# Wifinfo.net
KiCad netlist of a schematic drawn in EAGLE
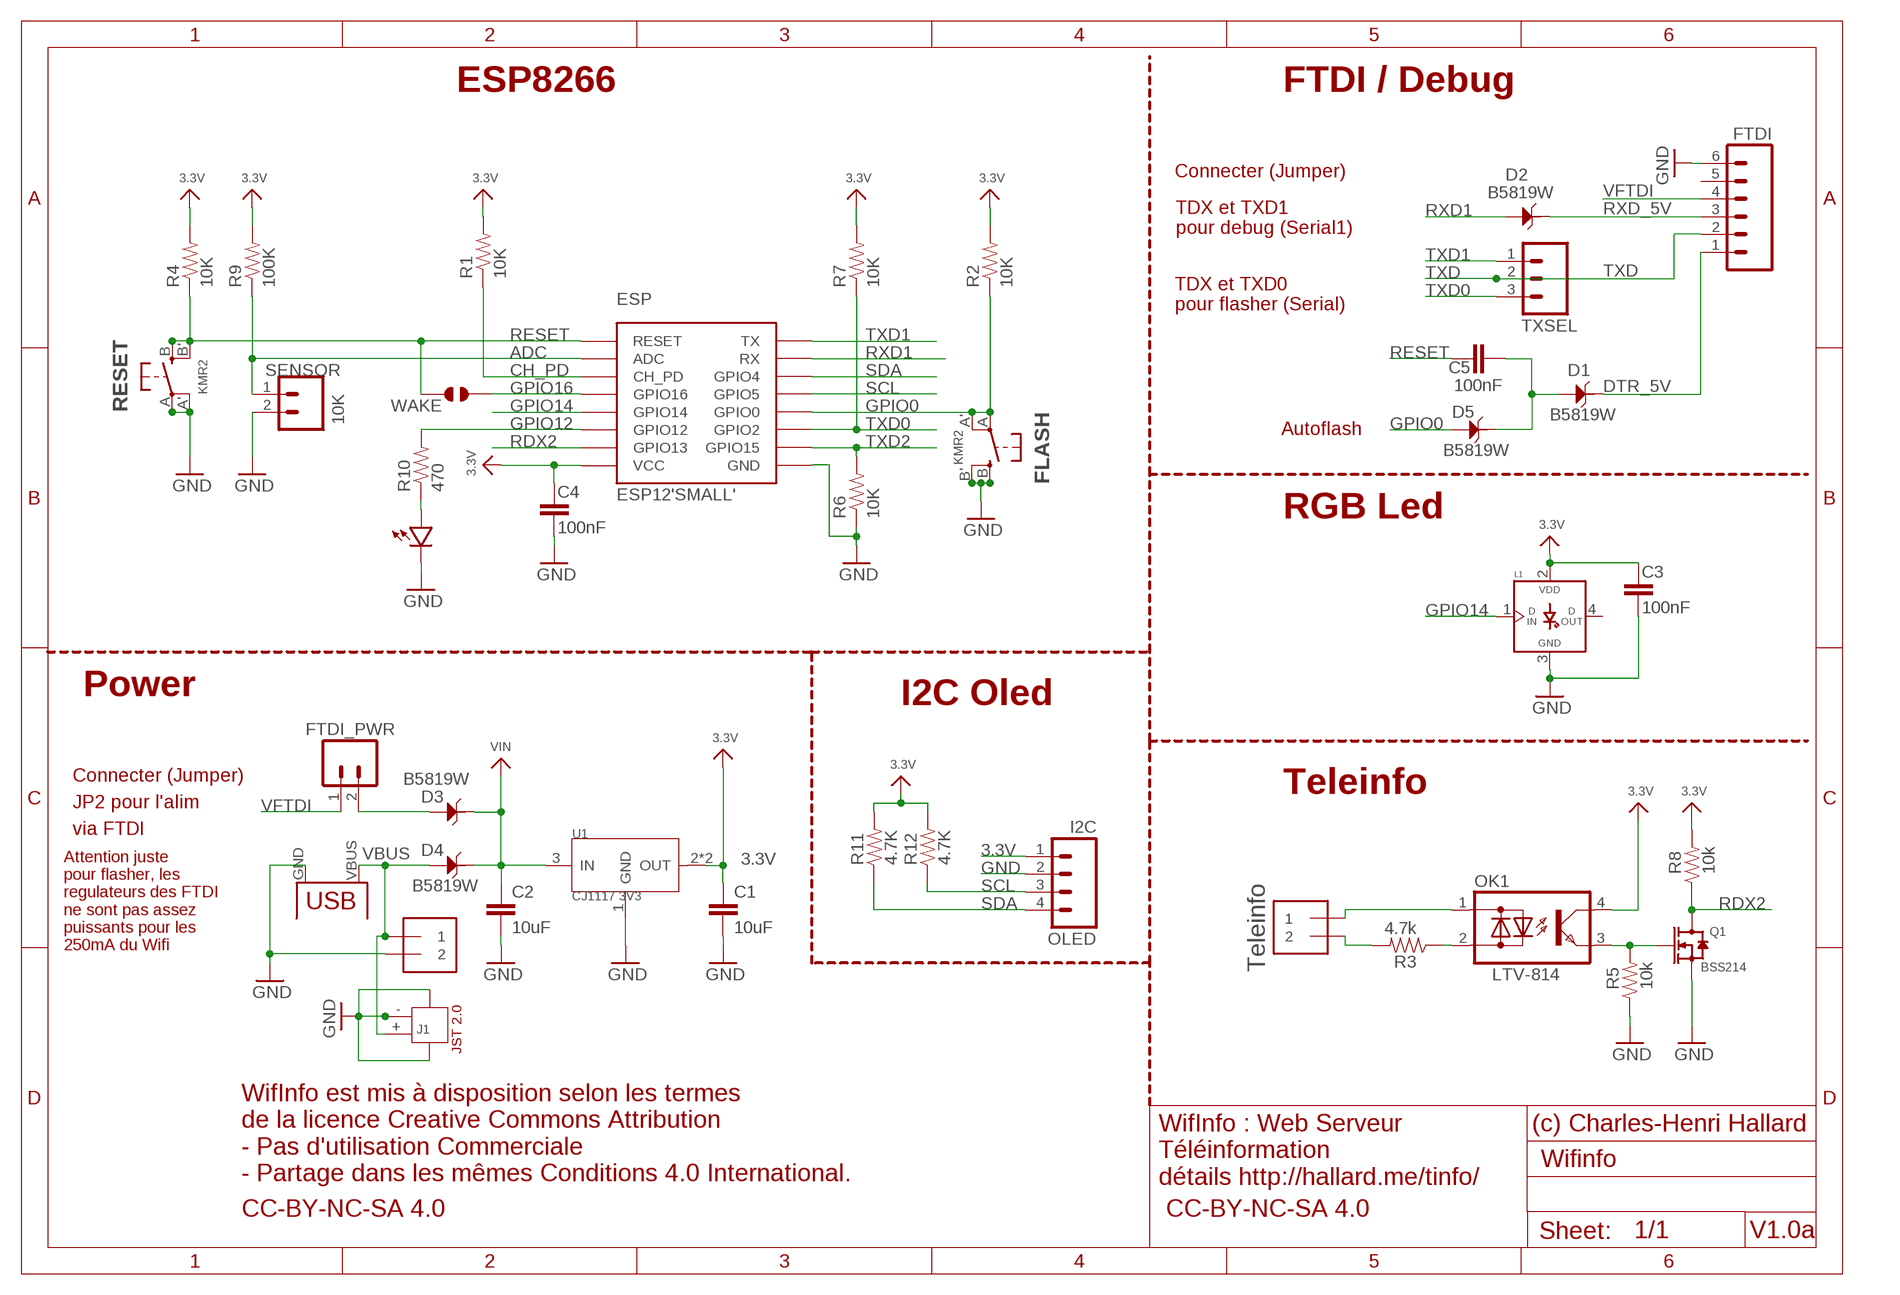
[diagram p0: schematic, sheet 1]

(export (version "E")
  (design (tool "Eeschema 10.0.6"))
  (components
    (comp (ref "C1")
      (value "10uF")
      (footprint "eagle-import:0805-CAP")
      (libsource (lib "eagle-import") (part "CAP0805-CAP"))
    )
    (comp (ref "C2")
      (value "10uF")
      (footprint "eagle-import:0805-CAP")
      (libsource (lib "eagle-import") (part "CAP0805-CAP"))
    )
    (comp (ref "C3")
      (value "100nF")
      (footprint "eagle-import:0603-CAP")
      (libsource (lib "eagle-import") (part "CAP0603-CAP"))
    )
    (comp (ref "C4")
      (value "100nF")
      (footprint "eagle-import:0603-CAP")
      (libsource (lib "eagle-import") (part "CAP0603-CAP"))
    )
    (comp (ref "C5")
      (value "100nF")
      (footprint "eagle-import:0603-CAP")
      (libsource (lib "eagle-import") (part "CAP0603-CAP"))
    )
    (comp (ref "D1")
      (value "B5819W")
      (footprint "eagle-import:SOD123-2.7X1.6")
      (libsource (lib "eagle-import") (part "D-ESD-2P-CESD5V0D1"))
    )
    (comp (ref "D2")
      (value "B5819W")
      (footprint "eagle-import:SOD123-2.7X1.6")
      (libsource (lib "eagle-import") (part "D-ESD-2P-CESD5V0D1"))
    )
    (comp (ref "D3")
      (value "B5819W")
      (footprint "eagle-import:SOD123-2.7X1.6")
      (libsource (lib "eagle-import") (part "D-ESD-2P-CESD5V0D1"))
    )
    (comp (ref "D4")
      (value "B5819W")
      (footprint "eagle-import:SOD123-2.7X1.6")
      (libsource (lib "eagle-import") (part "D-ESD-2P-CESD5V0D1"))
    )
    (comp (ref "D5")
      (value "B5819W")
      (footprint "eagle-import:SOD123-2.7X1.6")
      (libsource (lib "eagle-import") (part "D-ESD-2P-CESD5V0D1"))
    )
    (comp (ref "ESP")
      (value "ESP12'SMALL'")
      (footprint "eagle-import:ESP08")
      (libsource (lib "eagle-import") (part "ESP12'SMALL'"))
    )
    (comp (ref "FLASH")
      (value "KMR2")
      (footprint "eagle-import:BTN_KMR2_4.6X2.8")
      (libsource (lib "eagle-import") (part "SWITCH_TACT_SMT4.6X2.8"))
    )
    (comp (ref "FTDI")
      (value "M06SIP_LOCK_NO_SILK")
      (footprint "eagle-import:1X06-SIP_LOCK_NOSILK")
      (libsource (lib "eagle-import") (part "M06SIP_LOCK_NO_SILK"))
    )
    (comp (ref "FTDI_PWR")
      (value "M02LOCK")
      (footprint "eagle-import:1X02_LOCK")
      (libsource (lib "eagle-import") (part "M02LOCK"))
    )
    (comp (ref "J1")
      (value "JST-2P-SMD'2.0'")
      (footprint "eagle-import:2P-SMD-2.0-90D")
      (libsource (lib "eagle-import") (part "JST-2P-SMD'2.0'"))
    )
    (comp (ref "L1")
      (value "WS2812B")
      (footprint "eagle-import:WS2812-PTH")
      (libsource (lib "eagle-import") (part "WS2812B5MM"))
    )
    (comp (ref "LED")
      (value "RED")
      (footprint "eagle-import:0603-LED")
      (libsource (lib "eagle-import") (part "LED0603"))
    )
    (comp (ref "OK1")
      (value "LTV-814")
      (footprint "eagle-import:DIL4-SMD")
      (fields (field (name "MF") "VISHAY/TELEFUNKEN") (field (name "MPN") "SFH6206-3"))
      (libsource (lib "eagle-import") (part "SFH6206"))
    )
    (comp (ref "OLED")
      (value "I2C")
      (footprint "eagle-import:1X04_LOCK")
      (libsource (lib "eagle-import") (part "M04LOCK"))
    )
    (comp (ref "PWR")
      (value "1X2-3.5MM")
      (footprint "eagle-import:1X2-3.5MM")
      (libsource (lib "eagle-import") (part "1X2-3.5MM"))
    )
    (comp (ref "Q1")
      (value "BSS214")
      (footprint "eagle-import:SOT23")
      (libsource (lib "eagle-import") (part "MOSFET-N-''"))
    )
    (comp (ref "R1")
      (value "10K")
      (footprint "eagle-import:0603-RES")
      (libsource (lib "eagle-import") (part "RESISTOR0603-RES"))
    )
    (comp (ref "R2")
      (value "10K")
      (footprint "eagle-import:0603-RES")
      (libsource (lib "eagle-import") (part "RESISTOR0603-RES"))
    )
    (comp (ref "R3")
      (value "4.7k")
      (footprint "eagle-import:0603-RES")
      (libsource (lib "eagle-import") (part "RESISTOR0603-RES"))
    )
    (comp (ref "R4")
      (value "10K")
      (footprint "eagle-import:0603-RES")
      (libsource (lib "eagle-import") (part "RESISTOR0603-RES"))
    )
    (comp (ref "R5")
      (value "10k")
      (footprint "eagle-import:0603-RES")
      (libsource (lib "eagle-import") (part "RESISTOR0603-RES"))
    )
    (comp (ref "R6")
      (value "10K")
      (footprint "eagle-import:0603-RES")
      (libsource (lib "eagle-import") (part "RESISTOR0603-RES"))
    )
    (comp (ref "R7")
      (value "10K")
      (footprint "eagle-import:0603-RES")
      (libsource (lib "eagle-import") (part "RESISTOR0603-RES"))
    )
    (comp (ref "R8")
      (value "10k")
      (footprint "eagle-import:0603-RES")
      (libsource (lib "eagle-import") (part "RESISTOR0603-RES"))
    )
    (comp (ref "R9")
      (value "100K")
      (footprint "eagle-import:0805-RES")
      (libsource (lib "eagle-import") (part "RESISTOR0805-RES"))
    )
    (comp (ref "R10")
      (value "470")
      (footprint "eagle-import:0603-RES")
      (libsource (lib "eagle-import") (part "RESISTOR0603-RES"))
    )
    (comp (ref "R11")
      (value "4.7K")
      (footprint "eagle-import:0603-RES")
      (libsource (lib "eagle-import") (part "RESISTOR0603-RES"))
    )
    (comp (ref "R12")
      (value "4.7K")
      (footprint "eagle-import:0603-RES")
      (libsource (lib "eagle-import") (part "RESISTOR0603-RES"))
    )
    (comp (ref "RESET")
      (value "KMR2")
      (footprint "eagle-import:BTN_KMR2_4.6X2.8")
      (libsource (lib "eagle-import") (part "SWITCH_TACT_SMT4.6X2.8"))
    )
    (comp (ref "SENSOR")
      (value "10K")
      (footprint "eagle-import:1X02")
      (libsource (lib "eagle-import") (part "M02PTH"))
    )
    (comp (ref "TINFO")
      (value "1X2-3.5MM")
      (footprint "eagle-import:1X2-3.5MM")
      (libsource (lib "eagle-import") (part "1X2-3.5MM"))
    )
    (comp (ref "TXSEL")
      (value "M03LOCK")
      (footprint "eagle-import:1X03_LOCK")
      (libsource (lib "eagle-import") (part "M03LOCK"))
    )
    (comp (ref "U1")
      (value "CJ1117 3V3")
      (footprint "eagle-import:SOT89")
      (libsource (lib "eagle-import") (part "CJ1117-3.3-1310120P1"))
    )
    (comp (ref "USB")
      (value "USB")
      (footprint "eagle-import:USB_MINIB_POWER")
      (libsource (lib "eagle-import") (part "USB_POWER"))
    )
    (comp (ref "WAKE")
      (value "JUMPER_SOLDER_1X2")
      (footprint "eagle-import:JUMPER_SOLDER_1X2")
      (libsource (lib "eagle-import") (part "JUMPER_SOLDER_1X2"))
    )
  )
  (nets
    (net (code "1") (name "/ADC") (class "Default")
      (node (ref "ESP") (pin "ADC") (pinfunction "ADC_ADC") (pintype "bidirectional"))
      (node (ref "R9") (pin "1") (pinfunction "1_1") (pintype "passive"))
      (node (ref "SENSOR") (pin "1") (pinfunction "1_1") (pintype "passive"))
    )
    (net (code "2") (name "/CH_PD") (class "Default")
      (node (ref "ESP") (pin "CH_PD") (pinfunction "CH_PD_CH_PD") (pintype "bidirectional"))
      (node (ref "R1") (pin "1") (pinfunction "1_1") (pintype "passive"))
    )
    (net (code "3") (name "/DTR_5V") (class "Default")
      (node (ref "D1") (pin "2") (pinfunction "2_2") (pintype "bidirectional"))
      (node (ref "FTDI") (pin "1") (pinfunction "1_1") (pintype "passive"))
    )
    (net (code "4") (name "/GPIO0") (class "Default")
      (node (ref "D5") (pin "1") (pinfunction "1_1") (pintype "bidirectional"))
      (node (ref "ESP") (pin "GPIO0") (pinfunction "GPIO0_GPIO0") (pintype "bidirectional"))
      (node (ref "FLASH") (pin "A") (pinfunction "P_A") (pintype "passive"))
      (node (ref "FLASH") (pin "A'") (pinfunction "P1_A'") (pintype "passive"))
      (node (ref "R2") (pin "1") (pinfunction "1_1") (pintype "passive"))
    )
    (net (code "5") (name "/GPIO12") (class "Default")
      (node (ref "ESP") (pin "GPIO12") (pinfunction "GPIO12_GPIO12") (pintype "bidirectional"))
      (node (ref "R10") (pin "2") (pinfunction "2_2") (pintype "passive"))
    )
    (net (code "6") (name "/GPIO14") (class "Default")
      (node (ref "ESP") (pin "GPIO14") (pinfunction "GPIO14_GPIO14") (pintype "bidirectional"))
      (node (ref "L1") (pin "1") (pinfunction "DIN_1") (pintype "input"))
    )
    (net (code "7") (name "/GPIO16") (class "Default")
      (node (ref "ESP") (pin "GPIO16") (pinfunction "GPIO16_GPIO16") (pintype "bidirectional"))
      (node (ref "WAKE") (pin "2") (pinfunction "2_2") (pintype "passive"))
    )
    (net (code "8") (name "/RDX2") (class "Default")
      (node (ref "ESP") (pin "GPIO13") (pinfunction "GPIO13_GPIO13") (pintype "bidirectional"))
      (node (ref "Q1") (pin "3") (pinfunction "D_3") (pintype "passive"))
      (node (ref "R8") (pin "1") (pinfunction "1_1") (pintype "passive"))
    )
    (net (code "9") (name "/RESET") (class "Default")
      (node (ref "C5") (pin "2") (pinfunction "2_2") (pintype "passive"))
      (node (ref "ESP") (pin "RESET") (pinfunction "RESET_RESET") (pintype "bidirectional"))
      (node (ref "R4") (pin "1") (pinfunction "1_1") (pintype "passive"))
      (node (ref "RESET") (pin "B") (pinfunction "S_B") (pintype "passive"))
      (node (ref "RESET") (pin "B'") (pinfunction "S1_B'") (pintype "passive"))
      (node (ref "WAKE") (pin "1") (pinfunction "1_1") (pintype "passive"))
    )
    (net (code "10") (name "/RXD1") (class "Default")
      (node (ref "D2") (pin "1") (pinfunction "1_1") (pintype "bidirectional"))
      (node (ref "ESP") (pin "RX") (pinfunction "RX_RX") (pintype "bidirectional"))
    )
    (net (code "11") (name "/RXD_5V") (class "Default")
      (node (ref "D2") (pin "2") (pinfunction "2_2") (pintype "bidirectional"))
      (node (ref "FTDI") (pin "3") (pinfunction "3_3") (pintype "passive"))
    )
    (net (code "12") (name "/SCL") (class "Default")
      (node (ref "ESP") (pin "GPIO5") (pinfunction "GPIO5_GPIO5") (pintype "bidirectional"))
      (node (ref "OLED") (pin "3") (pinfunction "3_3") (pintype "passive"))
      (node (ref "R12") (pin "1") (pinfunction "1_1") (pintype "passive"))
    )
    (net (code "13") (name "/SDA") (class "Default")
      (node (ref "ESP") (pin "GPIO4") (pinfunction "GPIO4_GPIO4") (pintype "bidirectional"))
      (node (ref "OLED") (pin "4") (pinfunction "4_4") (pintype "passive"))
      (node (ref "R11") (pin "1") (pinfunction "1_1") (pintype "passive"))
    )
    (net (code "14") (name "/TXD") (class "Default")
      (node (ref "FTDI") (pin "2") (pinfunction "2_2") (pintype "passive"))
      (node (ref "TXSEL") (pin "2") (pinfunction "2_2") (pintype "passive"))
    )
    (net (code "15") (name "/TXD0") (class "Default")
      (node (ref "ESP") (pin "GPIO2") (pinfunction "GPIO2_GPIO2") (pintype "bidirectional"))
      (node (ref "R7") (pin "1") (pinfunction "1_1") (pintype "passive"))
      (node (ref "TXSEL") (pin "3") (pinfunction "3_3") (pintype "passive"))
    )
    (net (code "16") (name "/TXD1") (class "Default")
      (node (ref "ESP") (pin "TX") (pinfunction "TX_TX") (pintype "bidirectional"))
      (node (ref "TXSEL") (pin "1") (pinfunction "1_1") (pintype "passive"))
    )
    (net (code "17") (name "/TXD2") (class "Default")
      (node (ref "ESP") (pin "GPIO15") (pinfunction "GPIO15_GPIO15") (pintype "bidirectional"))
      (node (ref "R6") (pin "2") (pinfunction "2_2") (pintype "passive"))
    )
    (net (code "18") (name "/VBUS") (class "Default")
      (node (ref "D4") (pin "1") (pinfunction "1_1") (pintype "bidirectional"))
      (node (ref "J1") (pin "+") (pinfunction "1_+") (pintype "bidirectional"))
      (node (ref "PWR") (pin "1") (pinfunction "1_1") (pintype "passive"))
      (node (ref "USB") (pin "VBUS") (pinfunction "VCC_VBUS") (pintype "bidirectional"))
    )
    (net (code "19") (name "/VFTDI") (class "Default")
      (node (ref "FTDI") (pin "4") (pinfunction "4_4") (pintype "passive"))
      (node (ref "FTDI_PWR") (pin "1") (pinfunction "1_1") (pintype "passive"))
    )
    (net (code "20") (name "3.3V") (class "Default")
      (node (ref "C1") (pin "1") (pinfunction "1_1") (pintype "passive"))
      (node (ref "C3") (pin "2") (pinfunction "2_2") (pintype "passive"))
      (node (ref "C4") (pin "2") (pinfunction "2_2") (pintype "passive"))
      (node (ref "ESP") (pin "VCC") (pinfunction "VCC_VCC") (pintype "bidirectional"))
      (node (ref "L1") (pin "2") (pinfunction "VDD_2") (pintype "power_in"))
      (node (ref "OK1") (pin "4") (pinfunction "C_4") (pintype "passive"))
      (node (ref "OLED") (pin "1") (pinfunction "1_1") (pintype "passive"))
      (node (ref "R1") (pin "2") (pinfunction "2_2") (pintype "passive"))
      (node (ref "R11") (pin "2") (pinfunction "2_2") (pintype "passive"))
      (node (ref "R12") (pin "2") (pinfunction "2_2") (pintype "passive"))
      (node (ref "R2") (pin "2") (pinfunction "2_2") (pintype "passive"))
      (node (ref "R4") (pin "2") (pinfunction "2_2") (pintype "passive"))
      (node (ref "R7") (pin "2") (pinfunction "2_2") (pintype "passive"))
      (node (ref "R8") (pin "2") (pinfunction "2_2") (pintype "passive"))
      (node (ref "R9") (pin "2") (pinfunction "2_2") (pintype "passive"))
      (node (ref "U1") (pin "2") (pinfunction "OUT_2") (pintype "bidirectional"))
      (node (ref "U1") (pin "4") (pinfunction "OUT_4") (pintype "bidirectional"))
    )
    (net (code "21") (name "GND") (class "Default")
      (node (ref "C1") (pin "2") (pinfunction "2_2") (pintype "passive"))
      (node (ref "C2") (pin "2") (pinfunction "2_2") (pintype "passive"))
      (node (ref "C3") (pin "1") (pinfunction "1_1") (pintype "passive"))
      (node (ref "C4") (pin "1") (pinfunction "1_1") (pintype "passive"))
      (node (ref "ESP") (pin "GND") (pinfunction "GND_GND") (pintype "bidirectional"))
      (node (ref "FLASH") (pin "B") (pinfunction "S_B") (pintype "passive"))
      (node (ref "FLASH") (pin "B'") (pinfunction "S1_B'") (pintype "passive"))
      (node (ref "FTDI") (pin "6") (pinfunction "6_6") (pintype "passive"))
      (node (ref "J1") (pin "-") (pinfunction "2_-") (pintype "bidirectional"))
      (node (ref "J1") (pin "3") (pinfunction "3_3") (pintype "bidirectional"))
      (node (ref "J1") (pin "4") (pinfunction "4_4") (pintype "bidirectional"))
      (node (ref "L1") (pin "3") (pinfunction "GND_3") (pintype "power_in"))
      (node (ref "LED") (pin "MINUS") (pinfunction "MINUS_MINUS") (pintype "passive"))
      (node (ref "OLED") (pin "2") (pinfunction "2_2") (pintype "passive"))
      (node (ref "PWR") (pin "2") (pinfunction "2_2") (pintype "passive"))
      (node (ref "Q1") (pin "2") (pinfunction "S_2") (pintype "passive"))
      (node (ref "R5") (pin "1") (pinfunction "1_1") (pintype "passive"))
      (node (ref "R6") (pin "1") (pinfunction "1_1") (pintype "passive"))
      (node (ref "RESET") (pin "A") (pinfunction "P_A") (pintype "passive"))
      (node (ref "RESET") (pin "A'") (pinfunction "P1_A'") (pintype "passive"))
      (node (ref "SENSOR") (pin "2") (pinfunction "2_2") (pintype "passive"))
      (node (ref "U1") (pin "1") (pinfunction "GND_1") (pintype "bidirectional"))
      (node (ref "USB") (pin "GND") (pinfunction "GND_GND") (pintype "bidirectional"))
    )
    (net (code "22") (name "Net-(C5-Pad1)") (class "Default")
      (node (ref "C5") (pin "1") (pinfunction "1_1") (pintype "passive"))
      (node (ref "D1") (pin "1") (pinfunction "1_1") (pintype "bidirectional"))
      (node (ref "D5") (pin "2") (pinfunction "2_2") (pintype "bidirectional"))
    )
    (net (code "23") (name "Net-(D3-Pad1)") (class "Default")
      (node (ref "D3") (pin "1") (pinfunction "1_1") (pintype "bidirectional"))
      (node (ref "FTDI_PWR") (pin "2") (pinfunction "2_2") (pintype "passive"))
    )
    (net (code "24") (name "Net-(LED-PadPLUS)") (class "Default")
      (node (ref "LED") (pin "PLUS") (pinfunction "PLUS_PLUS") (pintype "passive"))
      (node (ref "R10") (pin "1") (pinfunction "1_1") (pintype "passive"))
    )
    (net (code "25") (name "Net-(OK1-AC1)") (class "Default")
      (node (ref "OK1") (pin "1") (pinfunction "AC1_1") (pintype "passive"))
      (node (ref "TINFO") (pin "1") (pinfunction "1_1") (pintype "passive"))
    )
    (net (code "26") (name "Net-(OK1-AC2)") (class "Default")
      (node (ref "OK1") (pin "2") (pinfunction "AC2_2") (pintype "passive"))
      (node (ref "R3") (pin "1") (pinfunction "1_1") (pintype "passive"))
    )
    (net (code "27") (name "Net-(OK1-E)") (class "Default")
      (node (ref "OK1") (pin "3") (pinfunction "E_3") (pintype "passive"))
      (node (ref "Q1") (pin "1") (pinfunction "G_1") (pintype "passive"))
      (node (ref "R5") (pin "2") (pinfunction "2_2") (pintype "passive"))
    )
    (net (code "28") (name "Net-(R3-Pad2)") (class "Default")
      (node (ref "R3") (pin "2") (pinfunction "2_2") (pintype "passive"))
      (node (ref "TINFO") (pin "2") (pinfunction "2_2") (pintype "passive"))
    )
    (net (code "29") (name "VIN") (class "Default")
      (node (ref "C2") (pin "1") (pinfunction "1_1") (pintype "passive"))
      (node (ref "D3") (pin "2") (pinfunction "2_2") (pintype "bidirectional"))
      (node (ref "D4") (pin "2") (pinfunction "2_2") (pintype "bidirectional"))
      (node (ref "U1") (pin "3") (pinfunction "IN_3") (pintype "bidirectional"))
    )
    (net (code "30") (name "unconnected-(FTDI-Pad5)") (class "Default")
      (node (ref "FTDI") (pin "5") (pinfunction "5_5") (pintype "passive"))
    )
    (net (code "31") (name "unconnected-(L1-DOUT-Pad4)") (class "Default")
      (node (ref "L1") (pin "4") (pinfunction "DOUT_4") (pintype "output"))
    )
  )
)
